# H0BR5_Backend.net
KiCad netlist of a schematic drawn in Altium Designer
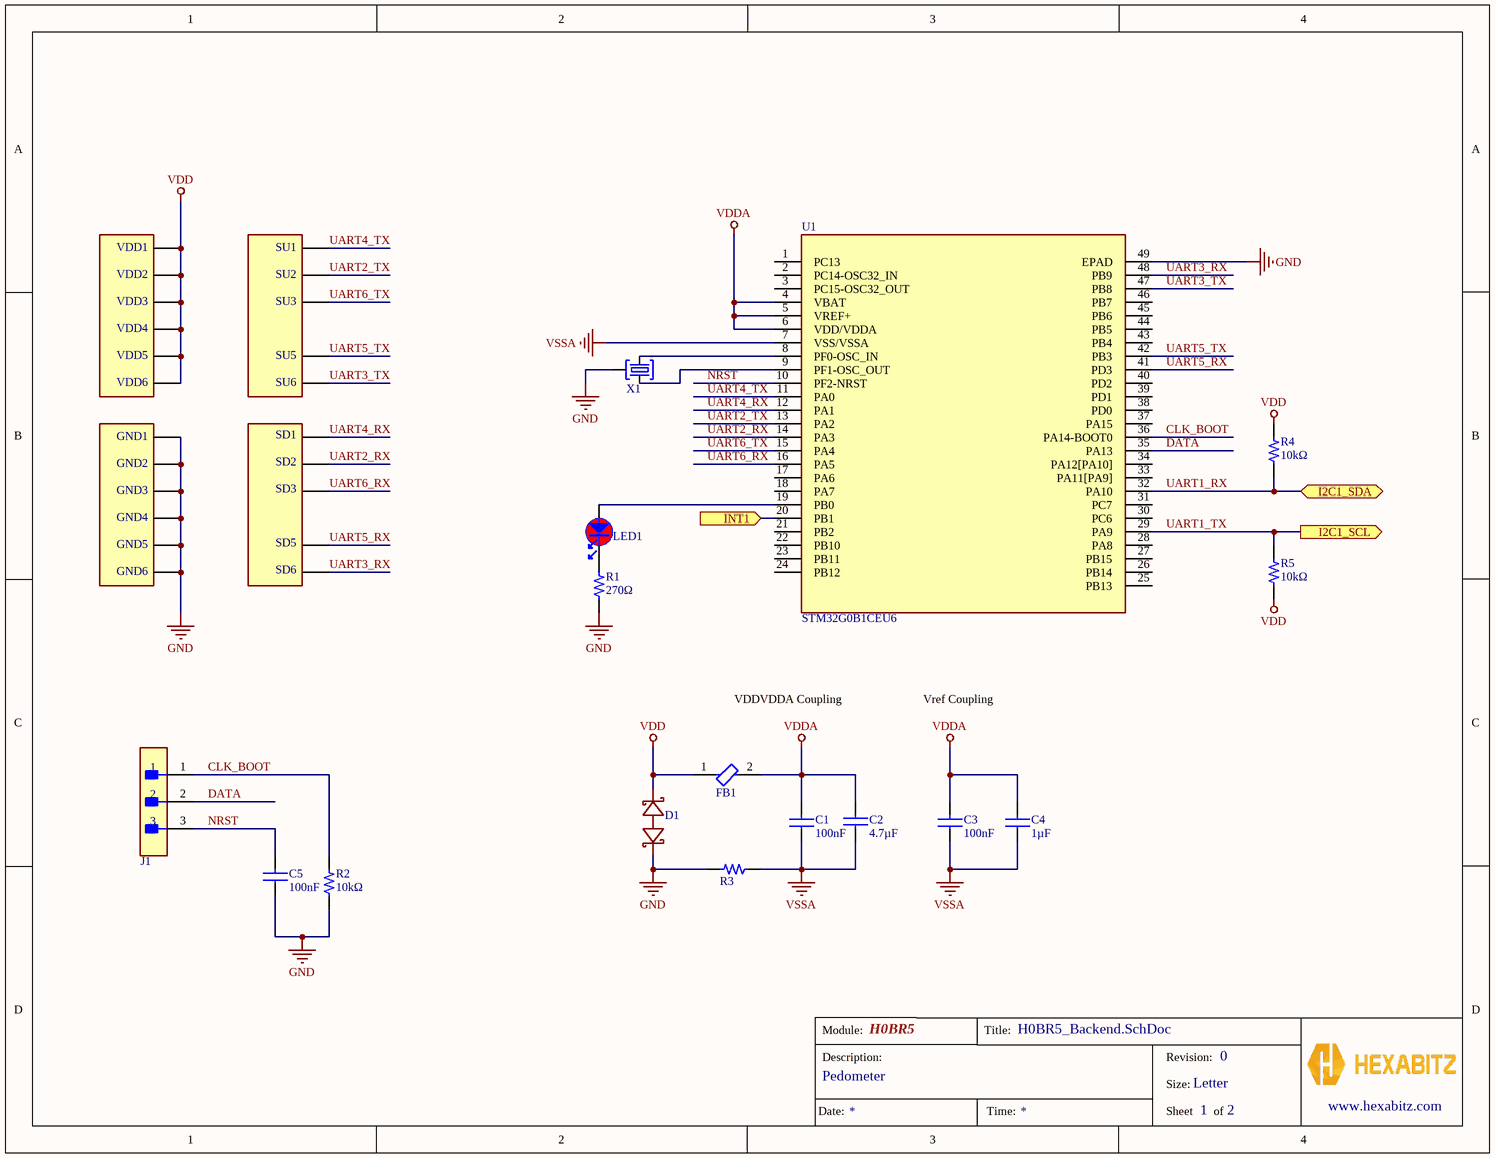
[diagram p0: H0BR5_Backend.SchDoc]

(export (version "E")
  (design (tool "Eeschema 10.0.6"))
  (components
    (comp (ref "C1")
      (value "100nF")
      (footprint "C0603")
      (fields
        (field (name "MANUFACTURER") "Samsung Electro-Mechanics")
        (field (name "MANUFACTURER PART NUMBER") "CL10B104KA8NNNC")
        (field (name "TOLERANCE") "10%")
      )
      (libsource (lib "Hexabitz Altium Library") (part "generic Capacitor"))
    )
    (comp (ref "C2")
      (value "4.7µF")
      (footprint "C0805")
      (fields
        (field (name "MANUFACTURER") "Samsung Electro-Mechanics")
        (field (name "MANUFACTURER PART NUMBER") "CL21X475KAQNNNE")
        (field (name "TOLERANCE") "10%")
      )
      (libsource (lib "Hexabitz Altium Library") (part "generic Capacitor"))
    )
    (comp (ref "C3")
      (value "100nF")
      (footprint "C0603")
      (fields
        (field (name "MANUFACTURER") "Samsung Electro-Mechanics")
        (field (name "MANUFACTURER PART NUMBER") "CL10B104KA8NNNC")
        (field (name "TOLERANCE") "10%")
      )
      (libsource (lib "Hexabitz Altium Library") (part "generic Capacitor"))
    )
    (comp (ref "C4")
      (value "1µF")
      (footprint "C0805")
      (description "Ceramic Capacitor, Ceramic, 16V, 10% +Tol, 10% -Tol, X7R, 15% TC, 1uF, Surface Mount, 0805")
      (fields
        (field (name "MANUFACTURER") "Yageo Group")
        (field (name "MANUFACTURER PART NUMBER") "CC0805KKX7R7BB105")
      )
      (libsource (lib "Hexabitz Altium Library") (part "generic Capacitor"))
    )
    (comp (ref "C5")
      (value "100nF")
      (footprint "C0603")
      (fields
        (field (name "MANUFACTURER") "Samsung Electro-Mechanics")
        (field (name "MANUFACTURER PART NUMBER") "CL10B104KA8NNNC")
        (field (name "TOLERANCE") "10%")
      )
      (libsource (lib "Hexabitz Altium Library") (part "generic Capacitor"))
    )
    (comp (ref "D1")
      (value "CDSOD323-T03SC")
      (footprint "SOD2513X114N")
      (description "A 3V, 350W, bi-directional, standard capacitance, SOD323 pkg TVS Diode ¦ Bourns CDSOD323-T03SC")
      (fields (field (name "MANUFACTURER") "Bourns"))
      (libsource (lib "Hexabitz Altium Library") (part "CDSOD323-T03SC"))
    )
    (comp (ref "FB1")
      (value "MMZ1608Y300B")
      (footprint "FP-MMZ1608-0_8-MFG")
      (description "Ferrite Beads 0603 30ohms 1500mA Signal Line AEC-Q200")
      (fields
        (field (name "MANUFACTURER") "TDK")
        (field (name "MANUFACTURER PART NUMBER") "MMZ1608Y300BTD25")
      )
      (libsource (lib "Hexabitz Altium Library") (part "MMZ1608Y300B"))
    )
    (comp (ref "GND1")
      (value "HEXABIT_UART_PORT")
      (footprint "HEXABIT_POWER_PORT_D")
      (libsource (lib "hexabitz_connectors.Library") (part "HEXABIT_POWER_PORT_D"))
    )
    (comp (ref "GND2")
      (value "HEXABIT_UART_PORT")
      (footprint "HEXABIT_POWER_PORT_D")
      (libsource (lib "hexabitz_connectors.Library") (part "HEXABIT_POWER_PORT_D"))
    )
    (comp (ref "GND3")
      (value "HEXABIT_UART_PORT")
      (footprint "HEXABIT_POWER_PORT_D")
      (libsource (lib "hexabitz_connectors.Library") (part "HEXABIT_POWER_PORT_D"))
    )
    (comp (ref "GND4")
      (value "HEXABIT_UART_PORT")
      (footprint "HEXABIT_POWER_PORT_D")
      (libsource (lib "hexabitz_connectors.Library") (part "HEXABIT_POWER_PORT_D"))
    )
    (comp (ref "GND5")
      (value "HEXABIT_UART_PORT")
      (footprint "HEXABIT_POWER_PORT_D")
      (libsource (lib "hexabitz_connectors.Library") (part "HEXABIT_POWER_PORT_D"))
    )
    (comp (ref "GND6")
      (value "HEXABIT_UART_PORT")
      (footprint "HEXABIT_POWER_PORT_D")
      (libsource (lib "hexabitz_connectors.Library") (part "HEXABIT_POWER_PORT_D"))
    )
    (comp (ref "J1")
      (value "TSW-103-14-G-S")
      (footprint "FP-TSW-103-14-G-S-MFG")
      (description "CONN HEADER VERT 3POS 2.54MM")
      (libsource (lib "Altium Content Vault") (part "cd3439d6ef35ae5d9b27ec4fdd3e828"))
    )
    (comp (ref "LED1")
      (value "VLMS1300-GS08")
      (footprint "FP-6_541-5092_01-4-MFG")
      (description "LED Uni-Color Super Red 639nm 2-Pin Chip 0603(1608Metric) T/R")
      (fields (field (name "MANUFACTURER") "Vishay Semiconductors"))
      (libsource (lib "Hexabitz Altium Library") (part "VLMS1300-GS08"))
    )
    (comp (ref "R1")
      (value "270Ω")
      (footprint "R0603")
      (description "Res Thick Film 0603 270 Ohm 5% 0.1W(1/10W) ±200ppm/C Pad SMD Automotive T/R")
      (fields
        (field (name "MANUFACTURER") "Panasonic")
        (field (name "MANUFACTURER PART NUMBER") "ERJ-3GEYJ271V")
      )
      (libsource (lib "Hexabitz Altium Library") (part "generic Resistor"))
    )
    (comp (ref "R2")
      (value "10kΩ")
      (footprint "R0603")
      (description "100mW Thick Film Resistors ±100ppm/℃ ±1% 10kΩ 0603 Chip Resistor - Surface Mount ROHS")
      (fields
        (field (name "MANUFACTURER") "Yageo Group")
        (field (name "MANUFACTURER PART NUMBER") "RC0603FR-0710KL")
      )
      (libsource (lib "") (part "generic Resistor_2"))
    )
    (comp (ref "R3")
      (value "Manufacturer Part Number")
      (footprint "R0603")
      (libsource (lib "") (part "generic Resistor_1"))
    )
    (comp (ref "R4")
      (value "10kΩ")
      (footprint "R0603")
      (description "100mW Thick Film Resistors ±100ppm/℃ ±1% 10kΩ 0603 Chip Resistor - Surface Mount ROHS")
      (fields
        (field (name "MANUFACTURER") "Yageo Group")
        (field (name "MANUFACTURER PART NUMBER") "RC0603FR-0710KL")
      )
      (libsource (lib "") (part "generic Resistor_2"))
    )
    (comp (ref "R5")
      (value "10kΩ")
      (footprint "R0603")
      (description "100mW Thick Film Resistors ±100ppm/℃ ±1% 10kΩ 0603 Chip Resistor - Surface Mount ROHS")
      (fields
        (field (name "MANUFACTURER") "Yageo Group")
        (field (name "MANUFACTURER PART NUMBER") "RC0603FR-0710KL")
      )
      (libsource (lib "") (part "generic Resistor_2"))
    )
    (comp (ref "SD1")
      (value "HEXABIT_UART_PORT")
      (footprint "HEXABIT_UART_PORT_D")
      (libsource (lib "hexabitz_connectors.Library") (part "HEXABIT_UART_PORT_D"))
    )
    (comp (ref "SD2")
      (value "HEXABIT_UART_PORT")
      (footprint "HEXABIT_UART_PORT_D")
      (libsource (lib "hexabitz_connectors.Library") (part "HEXABIT_UART_PORT_D"))
    )
    (comp (ref "SD3")
      (value "HEXABIT_UART_PORT")
      (footprint "HEXABIT_UART_PORT_D")
      (libsource (lib "hexabitz_connectors.Library") (part "HEXABIT_UART_PORT_D"))
    )
    (comp (ref "SD5")
      (value "HEXABIT_UART_PORT")
      (footprint "HEXABIT_UART_PORT_D")
      (libsource (lib "hexabitz_connectors.Library") (part "HEXABIT_UART_PORT_D"))
    )
    (comp (ref "SD6")
      (value "HEXABIT_UART_PORT")
      (footprint "HEXABIT_UART_PORT_D")
      (libsource (lib "hexabitz_connectors.Library") (part "HEXABIT_UART_PORT_D"))
    )
    (comp (ref "SU1")
      (value "HEXABIT_UART_PORT")
      (footprint "HEXABIT_UART_PORT_U")
      (libsource (lib "hexabitz_connectors.Library") (part "HEXABIT_UART_PORT_U"))
    )
    (comp (ref "SU2")
      (value "HEXABIT_UART_PORT")
      (footprint "HEXABIT_UART_PORT_U")
      (libsource (lib "hexabitz_connectors.Library") (part "HEXABIT_UART_PORT_U"))
    )
    (comp (ref "SU3")
      (value "HEXABIT_UART_PORT")
      (footprint "HEXABIT_UART_PORT_U")
      (libsource (lib "hexabitz_connectors.Library") (part "HEXABIT_UART_PORT_U"))
    )
    (comp (ref "SU5")
      (value "HEXABIT_UART_PORT")
      (footprint "HEXABIT_UART_PORT_U")
      (libsource (lib "hexabitz_connectors.Library") (part "HEXABIT_UART_PORT_U"))
    )
    (comp (ref "SU6")
      (value "HEXABIT_UART_PORT")
      (footprint "HEXABIT_UART_PORT_U")
      (libsource (lib "hexabitz_connectors.Library") (part "HEXABIT_UART_PORT_U"))
    )
    (comp (ref "U1")
      (value "STM32G0B1CEU6")
      (footprint "QFN50P700X700X65-49N-D")
      (description "MCU 32-bit ARM Cortex M0+ RISC 512KB Flash 1.8V/2.5V/3.3V 48-Pin UFQFPN EP Tray")
      (fields
        (field (name "MANUFACTURER") "STMicroelectronics")
        (field (name "MANUFACTURER PART NUMBER") "STM32G0B1CEU6")
      )
      (libsource (lib "Hexabitz Altium Library") (part "STM32G0B1CEU6"))
    )
    (comp (ref "VDD1")
      (value "HEXABIT_UART_PORT")
      (footprint "HEXABIT_POWER_PORT_U")
      (libsource (lib "hexabitz_connectors.Library") (part "HEXABIT_POWER_PORT_U"))
    )
    (comp (ref "VDD2")
      (value "HEXABIT_UART_PORT")
      (footprint "HEXABIT_POWER_PORT_U")
      (libsource (lib "hexabitz_connectors.Library") (part "HEXABIT_POWER_PORT_U"))
    )
    (comp (ref "VDD3")
      (value "HEXABIT_UART_PORT")
      (footprint "HEXABIT_POWER_PORT_U")
      (libsource (lib "hexabitz_connectors.Library") (part "HEXABIT_POWER_PORT_U"))
    )
    (comp (ref "VDD4")
      (value "HEXABIT_UART_PORT")
      (footprint "HEXABIT_POWER_PORT_U")
      (libsource (lib "hexabitz_connectors.Library") (part "HEXABIT_POWER_PORT_U"))
    )
    (comp (ref "VDD5")
      (value "HEXABIT_UART_PORT")
      (footprint "HEXABIT_POWER_PORT_U")
      (libsource (lib "hexabitz_connectors.Library") (part "HEXABIT_POWER_PORT_U"))
    )
    (comp (ref "VDD6")
      (value "HEXABIT_UART_PORT")
      (footprint "HEXABIT_POWER_PORT_U")
      (libsource (lib "hexabitz_connectors.Library") (part "HEXABIT_POWER_PORT_U"))
    )
    (comp (ref "X1")
      (value "CSTCE8M00G52Z-R0")
      (footprint "XTALL_CSTCE8M00G52")
      (description "Ceramic Resonator 8MHz ±0.5% (Tol) ±0.2% (Stability) 10pF 40Ohm 3-Pin CSMD T/R")
      (fields (field (name "MANUFACTURER") "Murata") (field (name "TOLERANCE") "0.5%"))
      (libsource (lib "Hexabitz Altium Library") (part "CSTCE8M00G52Z-R0"))
    )
  )
  (nets
    (net (code "1") (name "/CLK_BOOT") (class "Default")
      (node (ref "J1") (pin "1") (pinfunction "1_1") (pintype "passive"))
      (node (ref "R2") (pin "1") (pinfunction "1_1") (pintype "passive"))
      (node (ref "U1") (pin "36") (pinfunction "PA14-BOOT0_36") (pintype "passive"))
    )
    (net (code "2") (name "/DATA") (class "Default")
      (node (ref "J1") (pin "2") (pinfunction "2_2") (pintype "passive"))
      (node (ref "U1") (pin "35") (pinfunction "PA13_35") (pintype "passive"))
    )
    (net (code "3") (name "/INT1") (class "Default")
      (node (ref "U1") (pin "20") (pinfunction "PB1_20") (pintype "passive"))
    )
    (net (code "4") (name "/NRST") (class "Default")
      (node (ref "C5") (pin "2") (pinfunction "2_2") (pintype "passive"))
      (node (ref "J1") (pin "3") (pinfunction "3_3") (pintype "passive"))
      (node (ref "U1") (pin "10") (pinfunction "PF2-NRST_10") (pintype "passive"))
    )
    (net (code "5") (name "/UART1_RX") (class "Default")
      (node (ref "R4") (pin "2") (pinfunction "2_2") (pintype "passive"))
      (node (ref "U1") (pin "32") (pinfunction "PA10_32") (pintype "passive"))
    )
    (net (code "6") (name "/UART1_TX") (class "Default")
      (node (ref "R5") (pin "1") (pinfunction "1_1") (pintype "passive"))
      (node (ref "U1") (pin "29") (pinfunction "PA9_29") (pintype "passive"))
    )
    (net (code "7") (name "/UART2_RX") (class "Default")
      (node (ref "SD2") (pin "UART_D") (pinfunction "UART_D_UART_D") (pintype "passive"))
      (node (ref "U1") (pin "14") (pinfunction "PA3_14") (pintype "passive"))
    )
    (net (code "8") (name "/UART2_TX") (class "Default")
      (node (ref "SU2") (pin "UART_U") (pinfunction "UART_U_UART_U") (pintype "passive"))
      (node (ref "U1") (pin "13") (pinfunction "PA2_13") (pintype "passive"))
    )
    (net (code "9") (name "/UART3_RX") (class "Default")
      (node (ref "SD6") (pin "UART_D") (pinfunction "UART_D_UART_D") (pintype "passive"))
      (node (ref "U1") (pin "48") (pinfunction "PB9_48") (pintype "passive"))
    )
    (net (code "10") (name "/UART3_TX") (class "Default")
      (node (ref "SU6") (pin "UART_U") (pinfunction "UART_U_UART_U") (pintype "passive"))
      (node (ref "U1") (pin "47") (pinfunction "PB8_47") (pintype "passive"))
    )
    (net (code "11") (name "/UART4_RX") (class "Default")
      (node (ref "SD1") (pin "UART_D") (pinfunction "UART_D_UART_D") (pintype "passive"))
      (node (ref "U1") (pin "12") (pinfunction "PA1_12") (pintype "passive"))
    )
    (net (code "12") (name "/UART4_TX") (class "Default")
      (node (ref "SU1") (pin "UART_U") (pinfunction "UART_U_UART_U") (pintype "passive"))
      (node (ref "U1") (pin "11") (pinfunction "PA0_11") (pintype "passive"))
    )
    (net (code "13") (name "/UART5_RX") (class "Default")
      (node (ref "SD5") (pin "UART_D") (pinfunction "UART_D_UART_D") (pintype "passive"))
      (node (ref "U1") (pin "41") (pinfunction "PD3_41") (pintype "passive"))
    )
    (net (code "14") (name "/UART5_TX") (class "Default")
      (node (ref "SU5") (pin "UART_U") (pinfunction "UART_U_UART_U") (pintype "passive"))
      (node (ref "U1") (pin "42") (pinfunction "PB3_42") (pintype "passive"))
    )
    (net (code "15") (name "/UART6_RX") (class "Default")
      (node (ref "SD3") (pin "UART_D") (pinfunction "UART_D_UART_D") (pintype "passive"))
      (node (ref "U1") (pin "16") (pinfunction "PA5_16") (pintype "passive"))
    )
    (net (code "16") (name "/UART6_TX") (class "Default")
      (node (ref "SU3") (pin "UART_U") (pinfunction "UART_U_UART_U") (pintype "passive"))
      (node (ref "U1") (pin "15") (pinfunction "PA4_15") (pintype "passive"))
    )
    (net (code "17") (name "GND") (class "Default")
      (node (ref "C5") (pin "1") (pinfunction "1_1") (pintype "passive"))
      (node (ref "D1") (pin "1") (pinfunction "A_1") (pintype "passive"))
      (node (ref "GND1") (pin "Pwr_D") (pinfunction "Pwr_D_Pwr_D") (pintype "passive"))
      (node (ref "GND2") (pin "Pwr_D") (pinfunction "Pwr_D_Pwr_D") (pintype "passive"))
      (node (ref "GND3") (pin "Pwr_D") (pinfunction "Pwr_D_Pwr_D") (pintype "passive"))
      (node (ref "GND4") (pin "Pwr_D") (pinfunction "Pwr_D_Pwr_D") (pintype "passive"))
      (node (ref "GND5") (pin "Pwr_D") (pinfunction "Pwr_D_Pwr_D") (pintype "passive"))
      (node (ref "GND6") (pin "Pwr_D") (pinfunction "Pwr_D_Pwr_D") (pintype "passive"))
      (node (ref "R1") (pin "1") (pinfunction "1_1") (pintype "passive"))
      (node (ref "R2") (pin "2") (pinfunction "2_2") (pintype "passive"))
      (node (ref "R3") (pin "1") (pinfunction "1_1") (pintype "passive"))
      (node (ref "U1") (pin "49") (pinfunction "EPAD_49") (pintype "passive"))
      (node (ref "X1") (pin "P$2") (pinfunction "2_P$2") (pintype "passive"))
    )
    (net (code "18") (name "Net-(LED1-Pad1)") (class "Default")
      (node (ref "LED1") (pin "1") (pintype "passive"))
      (node (ref "R1") (pin "2") (pinfunction "2_2") (pintype "passive"))
    )
    (net (code "19") (name "Net-(U1-PB0)") (class "Default")
      (node (ref "LED1") (pin "2") (pintype "passive"))
      (node (ref "U1") (pin "19") (pinfunction "PB0_19") (pintype "passive"))
    )
    (net (code "20") (name "Net-(U1-PF0-OSC_IN)") (class "Default")
      (node (ref "U1") (pin "8") (pinfunction "PF0-OSC_IN_8") (pintype "passive"))
      (node (ref "X1") (pin "P$3") (pinfunction "3_P$3") (pintype "passive"))
    )
    (net (code "21") (name "Net-(U1-PF1-OSC_OUT)") (class "Default")
      (node (ref "U1") (pin "9") (pinfunction "PF1-OSC_OUT_9") (pintype "passive"))
      (node (ref "X1") (pin "P$1") (pinfunction "1_P$1") (pintype "passive"))
    )
    (net (code "22") (name "VDD") (class "Default")
      (node (ref "D1") (pin "2") (pinfunction "C_2") (pintype "passive"))
      (node (ref "FB1") (pin "1") (pinfunction "1_1") (pintype "passive"))
      (node (ref "R4") (pin "1") (pinfunction "1_1") (pintype "passive"))
      (node (ref "R5") (pin "2") (pinfunction "2_2") (pintype "passive"))
      (node (ref "VDD1") (pin "Pwr_U") (pinfunction "Pwr_U_Pwr_U") (pintype "passive"))
      (node (ref "VDD2") (pin "Pwr_U") (pinfunction "Pwr_U_Pwr_U") (pintype "passive"))
      (node (ref "VDD3") (pin "Pwr_U") (pinfunction "Pwr_U_Pwr_U") (pintype "passive"))
      (node (ref "VDD4") (pin "Pwr_U") (pinfunction "Pwr_U_Pwr_U") (pintype "passive"))
      (node (ref "VDD5") (pin "Pwr_U") (pinfunction "Pwr_U_Pwr_U") (pintype "passive"))
      (node (ref "VDD6") (pin "Pwr_U") (pinfunction "Pwr_U_Pwr_U") (pintype "passive"))
    )
    (net (code "23") (name "VDDA") (class "Default")
      (node (ref "C1") (pin "2") (pinfunction "2_2") (pintype "passive"))
      (node (ref "C2") (pin "1") (pinfunction "1_1") (pintype "passive"))
      (node (ref "C3") (pin "2") (pinfunction "2_2") (pintype "passive"))
      (node (ref "C4") (pin "2") (pinfunction "2_2") (pintype "passive"))
      (node (ref "FB1") (pin "2") (pinfunction "2_2") (pintype "passive"))
      (node (ref "U1") (pin "4") (pinfunction "VBAT_4") (pintype "passive"))
      (node (ref "U1") (pin "5") (pinfunction "VREF+_5") (pintype "passive"))
      (node (ref "U1") (pin "6") (pinfunction "VDD/VDDA_6") (pintype "passive"))
    )
    (net (code "24") (name "VSSA") (class "Default")
      (node (ref "C1") (pin "1") (pinfunction "1_1") (pintype "passive"))
      (node (ref "C2") (pin "2") (pinfunction "2_2") (pintype "passive"))
      (node (ref "C3") (pin "1") (pinfunction "1_1") (pintype "passive"))
      (node (ref "C4") (pin "1") (pinfunction "1_1") (pintype "passive"))
      (node (ref "R3") (pin "2") (pinfunction "2_2") (pintype "passive"))
      (node (ref "U1") (pin "7") (pinfunction "VSS/VSSA_7") (pintype "passive"))
    )
    (net (code "25") (name "unconnected-(U1-PA6-Pad17)") (class "Default")
      (node (ref "U1") (pin "17") (pinfunction "PA6_17") (pintype "passive"))
    )
    (net (code "26") (name "unconnected-(U1-PA7-Pad18)") (class "Default")
      (node (ref "U1") (pin "18") (pinfunction "PA7_18") (pintype "passive"))
    )
    (net (code "27") (name "unconnected-(U1-PA8-Pad28)") (class "Default")
      (node (ref "U1") (pin "28") (pinfunction "PA8_28") (pintype "passive"))
    )
    (net (code "28") (name "unconnected-(U1-PA11[PA9]-Pad33)") (class "Default")
      (node (ref "U1") (pin "33") (pinfunction "PA11[PA9]_33") (pintype "passive"))
    )
    (net (code "29") (name "unconnected-(U1-PA12[PA10]-Pad34)") (class "Default")
      (node (ref "U1") (pin "34") (pinfunction "PA12[PA10]_34") (pintype "passive"))
    )
    (net (code "30") (name "unconnected-(U1-PA15-Pad37)") (class "Default")
      (node (ref "U1") (pin "37") (pinfunction "PA15_37") (pintype "passive"))
    )
    (net (code "31") (name "unconnected-(U1-PB2-Pad21)") (class "Default")
      (node (ref "U1") (pin "21") (pinfunction "PB2_21") (pintype "passive"))
    )
    (net (code "32") (name "unconnected-(U1-PB4-Pad43)") (class "Default")
      (node (ref "U1") (pin "43") (pinfunction "PB4_43") (pintype "passive"))
    )
    (net (code "33") (name "unconnected-(U1-PB5-Pad44)") (class "Default")
      (node (ref "U1") (pin "44") (pinfunction "PB5_44") (pintype "passive"))
    )
    (net (code "34") (name "unconnected-(U1-PB6-Pad45)") (class "Default")
      (node (ref "U1") (pin "45") (pinfunction "PB6_45") (pintype "passive"))
    )
    (net (code "35") (name "unconnected-(U1-PB7-Pad46)") (class "Default")
      (node (ref "U1") (pin "46") (pinfunction "PB7_46") (pintype "passive"))
    )
    (net (code "36") (name "unconnected-(U1-PB10-Pad22)") (class "Default")
      (node (ref "U1") (pin "22") (pinfunction "PB10_22") (pintype "passive"))
    )
    (net (code "37") (name "unconnected-(U1-PB11-Pad23)") (class "Default")
      (node (ref "U1") (pin "23") (pinfunction "PB11_23") (pintype "passive"))
    )
    (net (code "38") (name "unconnected-(U1-PB12-Pad24)") (class "Default")
      (node (ref "U1") (pin "24") (pinfunction "PB12_24") (pintype "passive"))
    )
    (net (code "39") (name "unconnected-(U1-PB13-Pad25)") (class "Default")
      (node (ref "U1") (pin "25") (pinfunction "PB13_25") (pintype "passive"))
    )
    (net (code "40") (name "unconnected-(U1-PB14-Pad26)") (class "Default")
      (node (ref "U1") (pin "26") (pinfunction "PB14_26") (pintype "passive"))
    )
    (net (code "41") (name "unconnected-(U1-PB15-Pad27)") (class "Default")
      (node (ref "U1") (pin "27") (pinfunction "PB15_27") (pintype "passive"))
    )
    (net (code "42") (name "unconnected-(U1-PC6-Pad30)") (class "Default")
      (node (ref "U1") (pin "30") (pinfunction "PC6_30") (pintype "passive"))
    )
    (net (code "43") (name "unconnected-(U1-PC7-Pad31)") (class "Default")
      (node (ref "U1") (pin "31") (pinfunction "PC7_31") (pintype "passive"))
    )
    (net (code "44") (name "unconnected-(U1-PC13-Pad1)") (class "Default")
      (node (ref "U1") (pin "1") (pinfunction "PC13_1") (pintype "passive"))
    )
    (net (code "45") (name "unconnected-(U1-PC14-OSC32_IN-Pad2)") (class "Default")
      (node (ref "U1") (pin "2") (pinfunction "PC14-OSC32_IN_2") (pintype "passive"))
    )
    (net (code "46") (name "unconnected-(U1-PC15-OSC32_OUT-Pad3)") (class "Default")
      (node (ref "U1") (pin "3") (pinfunction "PC15-OSC32_OUT_3") (pintype "passive"))
    )
    (net (code "47") (name "unconnected-(U1-PD0-Pad38)") (class "Default")
      (node (ref "U1") (pin "38") (pinfunction "PD0_38") (pintype "passive"))
    )
    (net (code "48") (name "unconnected-(U1-PD1-Pad39)") (class "Default")
      (node (ref "U1") (pin "39") (pinfunction "PD1_39") (pintype "passive"))
    )
    (net (code "49") (name "unconnected-(U1-PD2-Pad40)") (class "Default")
      (node (ref "U1") (pin "40") (pinfunction "PD2_40") (pintype "passive"))
    )
  )
)
